# MECB_I2C_Board.net
KiCad netlist of a schematic drawn in EasyEDA
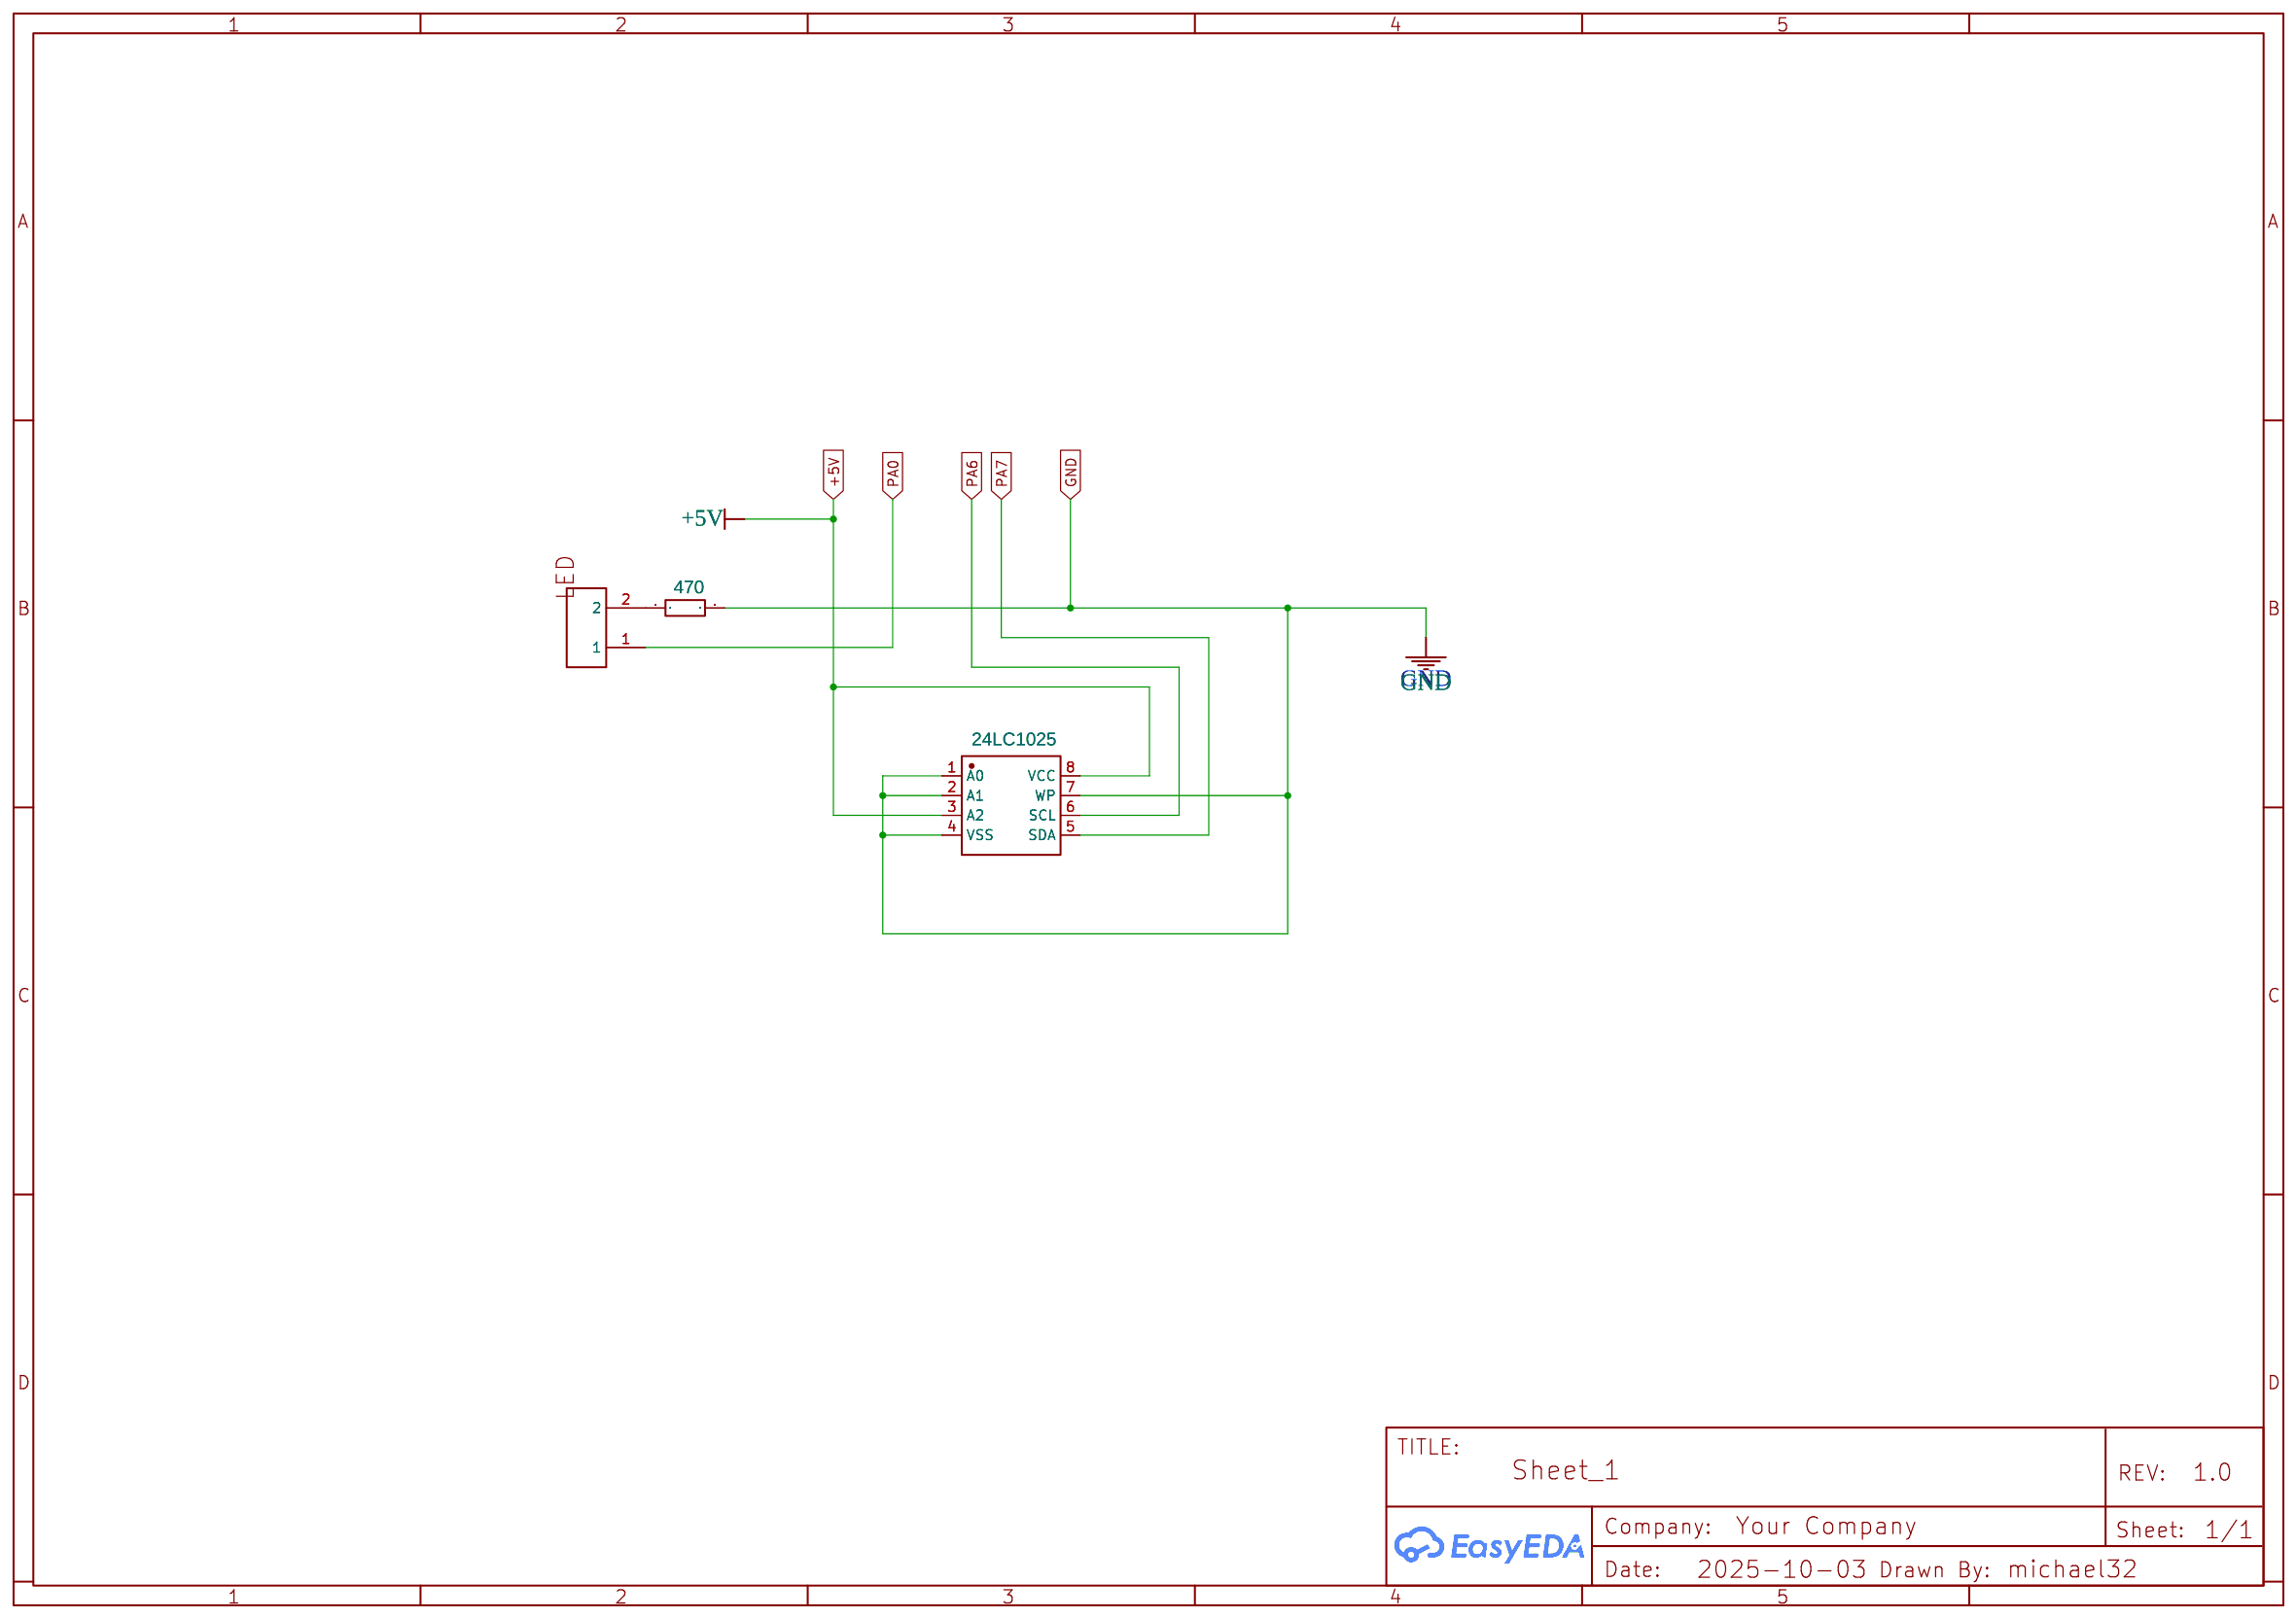
[diagram p0: schematic sheet]

(export (version "E")
  (design (tool "Eeschema 10.0.6"))
  (components
    (comp (ref "R7")
      (value "470")
      (fields (field (name "Manufacturer Part") "RES1/4W33R"))
      (libsource (lib "") (part "RES1/4W33R"))
    )
    (comp (ref "U12")
      (value "LED")
      (fields (field (name "Manufacturer Part") "YDXX-1X") (field (name "Manufacturer") "buddhika"))
      (libsource (lib "") (part "1x2 female header"))
    )
    (comp (ref "U13")
      (value "24LC1025")
      (fields
        (field (name "Manufacturer Part") "24AA1026-I/P")
        (field (name "Manufacturer") "MICROCHIP(美国微芯)")
      )
      (libsource (lib "") (part "24AA1026-I/P"))
    )
  )
  (nets
    (net (code "1") (name "+5V") (class "Default")
      (node (ref "U13") (pin "3") (pinfunction "A2_3") (pintype "unspecified"))
      (node (ref "U13") (pin "8") (pinfunction "VCC_8") (pintype "unspecified"))
    )
    (net (code "2") (name "GND") (class "Default")
      (node (ref "R7") (pin "2") (pinfunction "2_2") (pintype "unspecified"))
      (node (ref "U13") (pin "1") (pinfunction "A0_1") (pintype "unspecified"))
      (node (ref "U13") (pin "2") (pinfunction "A1_2") (pintype "unspecified"))
      (node (ref "U13") (pin "4") (pinfunction "VSS_4") (pintype "unspecified"))
      (node (ref "U13") (pin "7") (pinfunction "WP_7") (pintype "unspecified"))
    )
    (net (code "3") (name "Net-(R7-Pad1)") (class "Default")
      (node (ref "R7") (pin "1") (pinfunction "1_1") (pintype "unspecified"))
      (node (ref "U12") (pin "2") (pinfunction "2_2") (pintype "unspecified"))
    )
    (net (code "4") (name "PA0") (class "Default")
      (node (ref "U12") (pin "1") (pinfunction "1_1") (pintype "unspecified"))
    )
    (net (code "5") (name "PA6") (class "Default")
      (node (ref "U13") (pin "6") (pinfunction "SCL_6") (pintype "unspecified"))
    )
    (net (code "6") (name "PA7") (class "Default")
      (node (ref "U13") (pin "5") (pinfunction "SDA_5") (pintype "unspecified"))
    )
  )
)
